# Connector.net
KiCad netlist of a schematic drawn in Altium Designer
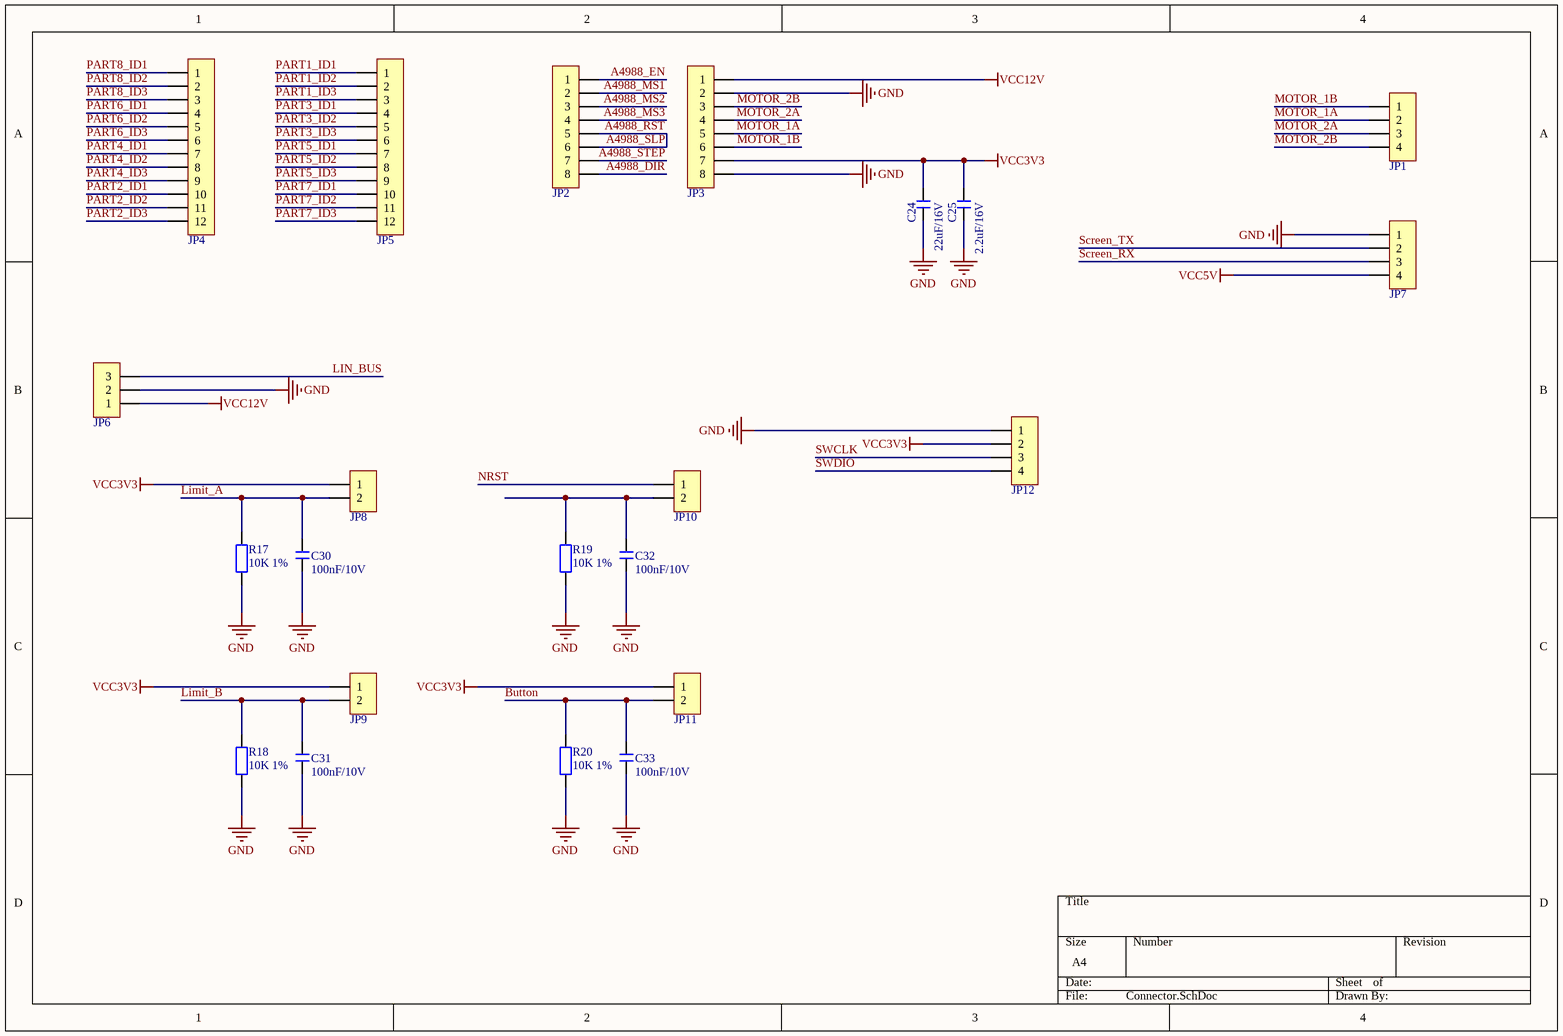
[diagram p0: Connector.SchDoc]

(export (version "E")
  (design (tool "Eeschema 10.0.6"))
  (components
    (comp (ref "C24")
      (value "22uF/16V")
      (footprint "C0603_L")
      (description "无极性贴片电容")
      (fields (field (name "版权归属") "源创客"))
      (libsource (lib "Capacitor") (part "C"))
    )
    (comp (ref "C25")
      (value "2.2uF/16V")
      (footprint "C0603_L")
      (description "无极性贴片电容")
      (fields (field (name "版权归属") "源创客"))
      (libsource (lib "Capacitor") (part "C"))
    )
    (comp (ref "C30")
      (value "100nF/10V")
      (footprint "C0603_L")
      (description "无极性贴片电容")
      (fields (field (name "版权归属") "源创客"))
      (libsource (lib "Capacitor") (part "C"))
    )
    (comp (ref "C31")
      (value "100nF/10V")
      (footprint "C0603_L")
      (description "无极性贴片电容")
      (fields (field (name "版权归属") "源创客"))
      (libsource (lib "Capacitor") (part "C"))
    )
    (comp (ref "C32")
      (value "100nF/10V")
      (footprint "C0603_L")
      (description "无极性贴片电容")
      (fields (field (name "版权归属") "源创客"))
      (libsource (lib "Capacitor") (part "C"))
    )
    (comp (ref "C33")
      (value "100nF/10V")
      (footprint "C0603_L")
      (description "无极性贴片电容")
      (fields (field (name "版权归属") "源创客"))
      (libsource (lib "Capacitor") (part "C"))
    )
    (comp (ref "JP1")
      (value "HDR-1X4")
      (footprint "XH2.54-LI-4P")
      (description "4P接插件")
      (fields (field (name "版权归属") "源创客"))
      (libsource (lib "Connector-PinHeader") (part "Header 4"))
    )
    (comp (ref "JP2")
      (value "HDR-1X8")
      (footprint "HDR2.54-M-LI-8P")
      (description "8P接插件")
      (fields (field (name "版权归属") "源创客"))
      (libsource (lib "Connector-PinHeader") (part "Header 8"))
    )
    (comp (ref "JP3")
      (value "HDR-1X8")
      (footprint "HDR2.54-M-LI-8P")
      (description "8P接插件")
      (fields (field (name "版权归属") "源创客"))
      (libsource (lib "Connector-PinHeader") (part "Header 8"))
    )
    (comp (ref "JP4")
      (value "HDR-1X12")
      (footprint "MX1.25-L-12P")
      (description "12P接插件")
      (fields (field (name "版权归属") "源创客"))
      (libsource (lib "Connector-PinHeader") (part "Header 12"))
    )
    (comp (ref "JP5")
      (value "HDR-1X12")
      (footprint "MX1.25-L-12P")
      (description "12P接插件")
      (fields (field (name "版权归属") "源创客"))
      (libsource (lib "Connector-PinHeader") (part "Header 12"))
    )
    (comp (ref "JP6")
      (value "HDR-1X3")
      (footprint "XH2.54-LI-3P")
      (description "3P接插件")
      (fields (field (name "版权归属") "源创客"))
      (libsource (lib "Connector-PinHeader") (part "Header 3"))
    )
    (comp (ref "JP7")
      (value "HDR-1X4")
      (footprint "XH2.54-LI-4P")
      (description "4P接插件")
      (fields (field (name "版权归属") "源创客"))
      (libsource (lib "Connector-PinHeader") (part "Header 4"))
    )
    (comp (ref "JP8")
      (value "HDR-1X2")
      (footprint "XH2.54-LI-2P")
      (description "2P接插件")
      (fields (field (name "版权归属") "源创客"))
      (libsource (lib "Connector-PinHeader") (part "Header 2"))
    )
    (comp (ref "JP9")
      (value "HDR-1X2")
      (footprint "XH2.54-LI-2P")
      (description "2P接插件")
      (fields (field (name "版权归属") "源创客"))
      (libsource (lib "Connector-PinHeader") (part "Header 2"))
    )
    (comp (ref "JP10")
      (value "HDR-1X2")
      (footprint "XH2.54-LI-2P")
      (description "2P接插件")
      (fields (field (name "版权归属") "源创客"))
      (libsource (lib "Connector-PinHeader") (part "Header 2"))
    )
    (comp (ref "JP11")
      (value "HDR-1X2")
      (footprint "XH2.54-LI-2P")
      (description "2P接插件")
      (fields (field (name "版权归属") "源创客"))
      (libsource (lib "Connector-PinHeader") (part "Header 2"))
    )
    (comp (ref "JP12")
      (value "HDR-1X4")
      (footprint "HDR2.54-LI-4P")
      (description "4P接插件")
      (fields (field (name "版权归属") "源创客"))
      (libsource (lib "Connector-PinHeader") (part "Header 4"))
    )
    (comp (ref "R17")
      (value "10K 1%")
      (footprint "R0603_L")
      (description "贴片电阻")
      (fields (field (name "版权归属") "源创客"))
      (libsource (lib "Resistor") (part "R"))
    )
    (comp (ref "R18")
      (value "10K 1%")
      (footprint "R0603_L")
      (description "贴片电阻")
      (fields (field (name "版权归属") "源创客"))
      (libsource (lib "Resistor") (part "R"))
    )
    (comp (ref "R19")
      (value "10K 1%")
      (footprint "R0603_L")
      (description "贴片电阻")
      (fields (field (name "版权归属") "源创客"))
      (libsource (lib "Resistor") (part "R"))
    )
    (comp (ref "R20")
      (value "10K 1%")
      (footprint "R0603_L")
      (description "贴片电阻")
      (fields (field (name "版权归属") "源创客"))
      (libsource (lib "Resistor") (part "R"))
    )
  )
  (nets
    (net (code "1") (name "/A4988_DIR") (class "Default")
      (node (ref "JP2") (pin "8") (pinfunction "8_8") (pintype "passive"))
    )
    (net (code "2") (name "/A4988_EN") (class "Default")
      (node (ref "JP2") (pin "1") (pinfunction "1_1") (pintype "passive"))
    )
    (net (code "3") (name "/A4988_MS1") (class "Default")
      (node (ref "JP2") (pin "2") (pinfunction "2_2") (pintype "passive"))
    )
    (net (code "4") (name "/A4988_MS2") (class "Default")
      (node (ref "JP2") (pin "3") (pinfunction "3_3") (pintype "passive"))
    )
    (net (code "5") (name "/A4988_MS3") (class "Default")
      (node (ref "JP2") (pin "4") (pinfunction "4_4") (pintype "passive"))
    )
    (net (code "6") (name "/A4988_RST") (class "Default")
      (node (ref "JP2") (pin "5") (pinfunction "5_5") (pintype "passive"))
      (node (ref "JP2") (pin "6") (pinfunction "6_6") (pintype "passive"))
    )
    (net (code "7") (name "/A4988_STEP") (class "Default")
      (node (ref "JP2") (pin "7") (pinfunction "7_7") (pintype "passive"))
    )
    (net (code "8") (name "/Button") (class "Default")
      (node (ref "C33") (pin "1") (pinfunction "1_1") (pintype "passive"))
      (node (ref "JP11") (pin "2") (pinfunction "2_2") (pintype "passive"))
      (node (ref "R20") (pin "1") (pinfunction "1_1") (pintype "passive"))
    )
    (net (code "9") (name "/LIN_BUS") (class "Default")
      (node (ref "JP6") (pin "3") (pinfunction "3_3") (pintype "passive"))
    )
    (net (code "10") (name "/Limit_A") (class "Default")
      (node (ref "C30") (pin "1") (pinfunction "1_1") (pintype "passive"))
      (node (ref "JP8") (pin "2") (pinfunction "2_2") (pintype "passive"))
      (node (ref "R17") (pin "1") (pinfunction "1_1") (pintype "passive"))
    )
    (net (code "11") (name "/Limit_B") (class "Default")
      (node (ref "C31") (pin "1") (pinfunction "1_1") (pintype "passive"))
      (node (ref "JP9") (pin "2") (pinfunction "2_2") (pintype "passive"))
      (node (ref "R18") (pin "1") (pinfunction "1_1") (pintype "passive"))
    )
    (net (code "12") (name "/MOTOR_1A") (class "Default")
      (node (ref "JP1") (pin "2") (pinfunction "2_2") (pintype "passive"))
      (node (ref "JP3") (pin "5") (pinfunction "5_5") (pintype "passive"))
    )
    (net (code "13") (name "/MOTOR_1B") (class "Default")
      (node (ref "JP1") (pin "1") (pinfunction "1_1") (pintype "passive"))
      (node (ref "JP3") (pin "6") (pinfunction "6_6") (pintype "passive"))
    )
    (net (code "14") (name "/MOTOR_2A") (class "Default")
      (node (ref "JP1") (pin "3") (pinfunction "3_3") (pintype "passive"))
      (node (ref "JP3") (pin "4") (pinfunction "4_4") (pintype "passive"))
    )
    (net (code "15") (name "/MOTOR_2B") (class "Default")
      (node (ref "JP1") (pin "4") (pinfunction "4_4") (pintype "passive"))
      (node (ref "JP3") (pin "3") (pinfunction "3_3") (pintype "passive"))
    )
    (net (code "16") (name "/NRST") (class "Default")
      (node (ref "JP10") (pin "1") (pinfunction "1_1") (pintype "passive"))
    )
    (net (code "17") (name "/PART1_ID1") (class "Default")
      (node (ref "JP5") (pin "1") (pinfunction "1_1") (pintype "passive"))
    )
    (net (code "18") (name "/PART1_ID2") (class "Default")
      (node (ref "JP5") (pin "2") (pinfunction "2_2") (pintype "passive"))
    )
    (net (code "19") (name "/PART1_ID3") (class "Default")
      (node (ref "JP5") (pin "3") (pinfunction "3_3") (pintype "passive"))
    )
    (net (code "20") (name "/PART2_ID1") (class "Default")
      (node (ref "JP4") (pin "10") (pinfunction "10_10") (pintype "passive"))
    )
    (net (code "21") (name "/PART2_ID2") (class "Default")
      (node (ref "JP4") (pin "11") (pinfunction "11_11") (pintype "passive"))
    )
    (net (code "22") (name "/PART2_ID3") (class "Default")
      (node (ref "JP4") (pin "12") (pinfunction "12_12") (pintype "passive"))
    )
    (net (code "23") (name "/PART3_ID1") (class "Default")
      (node (ref "JP5") (pin "4") (pinfunction "4_4") (pintype "passive"))
    )
    (net (code "24") (name "/PART3_ID2") (class "Default")
      (node (ref "JP5") (pin "5") (pinfunction "5_5") (pintype "passive"))
    )
    (net (code "25") (name "/PART3_ID3") (class "Default")
      (node (ref "JP5") (pin "6") (pinfunction "6_6") (pintype "passive"))
    )
    (net (code "26") (name "/PART4_ID1") (class "Default")
      (node (ref "JP4") (pin "7") (pinfunction "7_7") (pintype "passive"))
    )
    (net (code "27") (name "/PART4_ID2") (class "Default")
      (node (ref "JP4") (pin "8") (pinfunction "8_8") (pintype "passive"))
    )
    (net (code "28") (name "/PART4_ID3") (class "Default")
      (node (ref "JP4") (pin "9") (pinfunction "9_9") (pintype "passive"))
    )
    (net (code "29") (name "/PART5_ID1") (class "Default")
      (node (ref "JP5") (pin "7") (pinfunction "7_7") (pintype "passive"))
    )
    (net (code "30") (name "/PART5_ID2") (class "Default")
      (node (ref "JP5") (pin "8") (pinfunction "8_8") (pintype "passive"))
    )
    (net (code "31") (name "/PART5_ID3") (class "Default")
      (node (ref "JP5") (pin "9") (pinfunction "9_9") (pintype "passive"))
    )
    (net (code "32") (name "/PART6_ID1") (class "Default")
      (node (ref "JP4") (pin "4") (pinfunction "4_4") (pintype "passive"))
    )
    (net (code "33") (name "/PART6_ID2") (class "Default")
      (node (ref "JP4") (pin "5") (pinfunction "5_5") (pintype "passive"))
    )
    (net (code "34") (name "/PART6_ID3") (class "Default")
      (node (ref "JP4") (pin "6") (pinfunction "6_6") (pintype "passive"))
    )
    (net (code "35") (name "/PART7_ID1") (class "Default")
      (node (ref "JP5") (pin "10") (pinfunction "10_10") (pintype "passive"))
    )
    (net (code "36") (name "/PART7_ID2") (class "Default")
      (node (ref "JP5") (pin "11") (pinfunction "11_11") (pintype "passive"))
    )
    (net (code "37") (name "/PART7_ID3") (class "Default")
      (node (ref "JP5") (pin "12") (pinfunction "12_12") (pintype "passive"))
    )
    (net (code "38") (name "/PART8_ID1") (class "Default")
      (node (ref "JP4") (pin "1") (pinfunction "1_1") (pintype "passive"))
    )
    (net (code "39") (name "/PART8_ID2") (class "Default")
      (node (ref "JP4") (pin "2") (pinfunction "2_2") (pintype "passive"))
    )
    (net (code "40") (name "/PART8_ID3") (class "Default")
      (node (ref "JP4") (pin "3") (pinfunction "3_3") (pintype "passive"))
    )
    (net (code "41") (name "/SWCLK") (class "Default")
      (node (ref "JP12") (pin "3") (pinfunction "3_3") (pintype "passive"))
    )
    (net (code "42") (name "/SWDIO") (class "Default")
      (node (ref "JP12") (pin "4") (pinfunction "4_4") (pintype "passive"))
    )
    (net (code "43") (name "/Screen_RX") (class "Default")
      (node (ref "JP7") (pin "3") (pinfunction "3_3") (pintype "passive"))
    )
    (net (code "44") (name "/Screen_TX") (class "Default")
      (node (ref "JP7") (pin "2") (pinfunction "2_2") (pintype "passive"))
    )
    (net (code "45") (name "GND") (class "Default")
      (node (ref "C24") (pin "1") (pinfunction "1_1") (pintype "passive"))
      (node (ref "C25") (pin "1") (pinfunction "1_1") (pintype "passive"))
      (node (ref "C30") (pin "2") (pinfunction "2_2") (pintype "passive"))
      (node (ref "C31") (pin "2") (pinfunction "2_2") (pintype "passive"))
      (node (ref "C32") (pin "2") (pinfunction "2_2") (pintype "passive"))
      (node (ref "C33") (pin "2") (pinfunction "2_2") (pintype "passive"))
      (node (ref "JP12") (pin "1") (pinfunction "1_1") (pintype "passive"))
      (node (ref "JP3") (pin "2") (pinfunction "2_2") (pintype "passive"))
      (node (ref "JP3") (pin "8") (pinfunction "8_8") (pintype "passive"))
      (node (ref "JP6") (pin "2") (pinfunction "2_2") (pintype "passive"))
      (node (ref "JP7") (pin "1") (pinfunction "1_1") (pintype "passive"))
      (node (ref "R17") (pin "2") (pinfunction "2_2") (pintype "passive"))
      (node (ref "R18") (pin "2") (pinfunction "2_2") (pintype "passive"))
      (node (ref "R19") (pin "2") (pinfunction "2_2") (pintype "passive"))
      (node (ref "R20") (pin "2") (pinfunction "2_2") (pintype "passive"))
    )
    (net (code "46") (name "Net-(C32-Pad1)") (class "Default")
      (node (ref "C32") (pin "1") (pinfunction "1_1") (pintype "passive"))
      (node (ref "JP10") (pin "2") (pinfunction "2_2") (pintype "passive"))
      (node (ref "R19") (pin "1") (pinfunction "1_1") (pintype "passive"))
    )
    (net (code "47") (name "VCC3V3") (class "Default")
      (node (ref "C24") (pin "2") (pinfunction "2_2") (pintype "passive"))
      (node (ref "C25") (pin "2") (pinfunction "2_2") (pintype "passive"))
      (node (ref "JP11") (pin "1") (pinfunction "1_1") (pintype "passive"))
      (node (ref "JP12") (pin "2") (pinfunction "2_2") (pintype "passive"))
      (node (ref "JP3") (pin "7") (pinfunction "7_7") (pintype "passive"))
      (node (ref "JP8") (pin "1") (pinfunction "1_1") (pintype "passive"))
      (node (ref "JP9") (pin "1") (pinfunction "1_1") (pintype "passive"))
    )
    (net (code "48") (name "VCC5V") (class "Default")
      (node (ref "JP7") (pin "4") (pinfunction "4_4") (pintype "passive"))
    )
    (net (code "49") (name "VCC12V") (class "Default")
      (node (ref "JP3") (pin "1") (pinfunction "1_1") (pintype "passive"))
      (node (ref "JP6") (pin "1") (pinfunction "1_1") (pintype "passive"))
    )
  )
)
